# LiPoBatteryBreakout.net
KiCad netlist of a schematic drawn in EAGLE
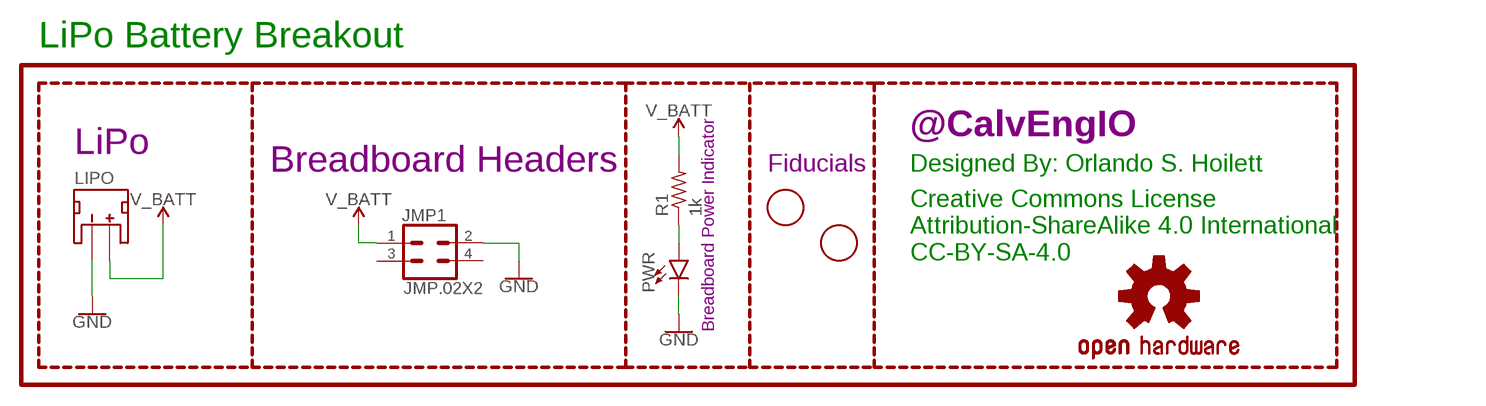
[diagram p0: schematic, sheet 1]

(export (version "E")
  (design (tool "Eeschema 10.0.6"))
  (components
    (comp (ref "FD1")
      (value "FIDUCIAL")
      (footprint "eagle-import:FIDUCIAL_1MM")
      (libsource (lib "eagle-import") (part "FIDUCIAL"))
    )
    (comp (ref "FD2")
      (value "FIDUCIAL")
      (footprint "eagle-import:FIDUCIAL_1MM")
      (libsource (lib "eagle-import") (part "FIDUCIAL"))
    )
    (comp (ref "JMP1")
      (value "JMP.02X2")
      (footprint "eagle-import:JMP.02X2")
      (libsource (lib "eagle-import") (part "JMP.02X2"))
    )
    (comp (ref "LIPO")
      (value "JST_2MM_MALE")
      (footprint "eagle-import:JST-2-SMD")
      (libsource (lib "eagle-import") (part "JST_2MM_MALE"))
    )
    (comp (ref "LOGO1")
      (value "OSHW-LOGOS")
      (footprint "eagle-import:OSHW-LOGO-S")
      (libsource (lib "eagle-import") (part "OSHW-LOGOS"))
    )
    (comp (ref "PWR")
      (value "LED0603")
      (footprint "eagle-import:LED-0603")
      (libsource (lib "eagle-import") (part "LED0603"))
    )
    (comp (ref "R1")
      (value "1k")
      (footprint "eagle-import:R0402")
      (libsource (lib "eagle-import") (part "R-US_R0402"))
    )
    (comp (ref "U$2")
      (value "LOGO.05")
      (footprint "eagle-import:LOGO.05")
      (libsource (lib "eagle-import") (part "LOGO.05"))
    )
  )
  (nets
    (net (code "1") (name "GND") (class "Default")
      (node (ref "JMP1") (pin "2") (pinfunction "2_2") (pintype "passive"))
      (node (ref "LIPO") (pin "1") (pinfunction "-_1") (pintype "bidirectional"))
      (node (ref "PWR") (pin "C") (pinfunction "C_C") (pintype "passive"))
    )
    (net (code "2") (name "Net-(PWR-PadA)") (class "Default")
      (node (ref "PWR") (pin "A") (pinfunction "A_A") (pintype "passive"))
      (node (ref "R1") (pin "1") (pinfunction "1_1") (pintype "passive"))
    )
    (net (code "3") (name "V_BATT") (class "Default")
      (node (ref "JMP1") (pin "1") (pinfunction "1_1") (pintype "passive"))
      (node (ref "LIPO") (pin "2") (pinfunction "+_2") (pintype "bidirectional"))
      (node (ref "R1") (pin "2") (pinfunction "2_2") (pintype "passive"))
    )
    (net (code "4") (name "unconnected-(JMP1-Pad3)") (class "Default")
      (node (ref "JMP1") (pin "3") (pinfunction "3_3") (pintype "passive"))
    )
    (net (code "5") (name "unconnected-(JMP1-Pad4)") (class "Default")
      (node (ref "JMP1") (pin "4") (pinfunction "4_4") (pintype "passive"))
    )
    (net (code "6") (name "unconnected-(LIPO-PAD1-PadNC1)") (class "Default")
      (node (ref "LIPO") (pin "NC1") (pinfunction "PAD1_NC1") (pintype "bidirectional"))
    )
    (net (code "7") (name "unconnected-(LIPO-PAD2-PadNC2)") (class "Default")
      (node (ref "LIPO") (pin "NC2") (pinfunction "PAD2_NC2") (pintype "bidirectional"))
    )
  )
)
